# tx_board.net
KiCad netlist of a schematic drawn in EAGLE
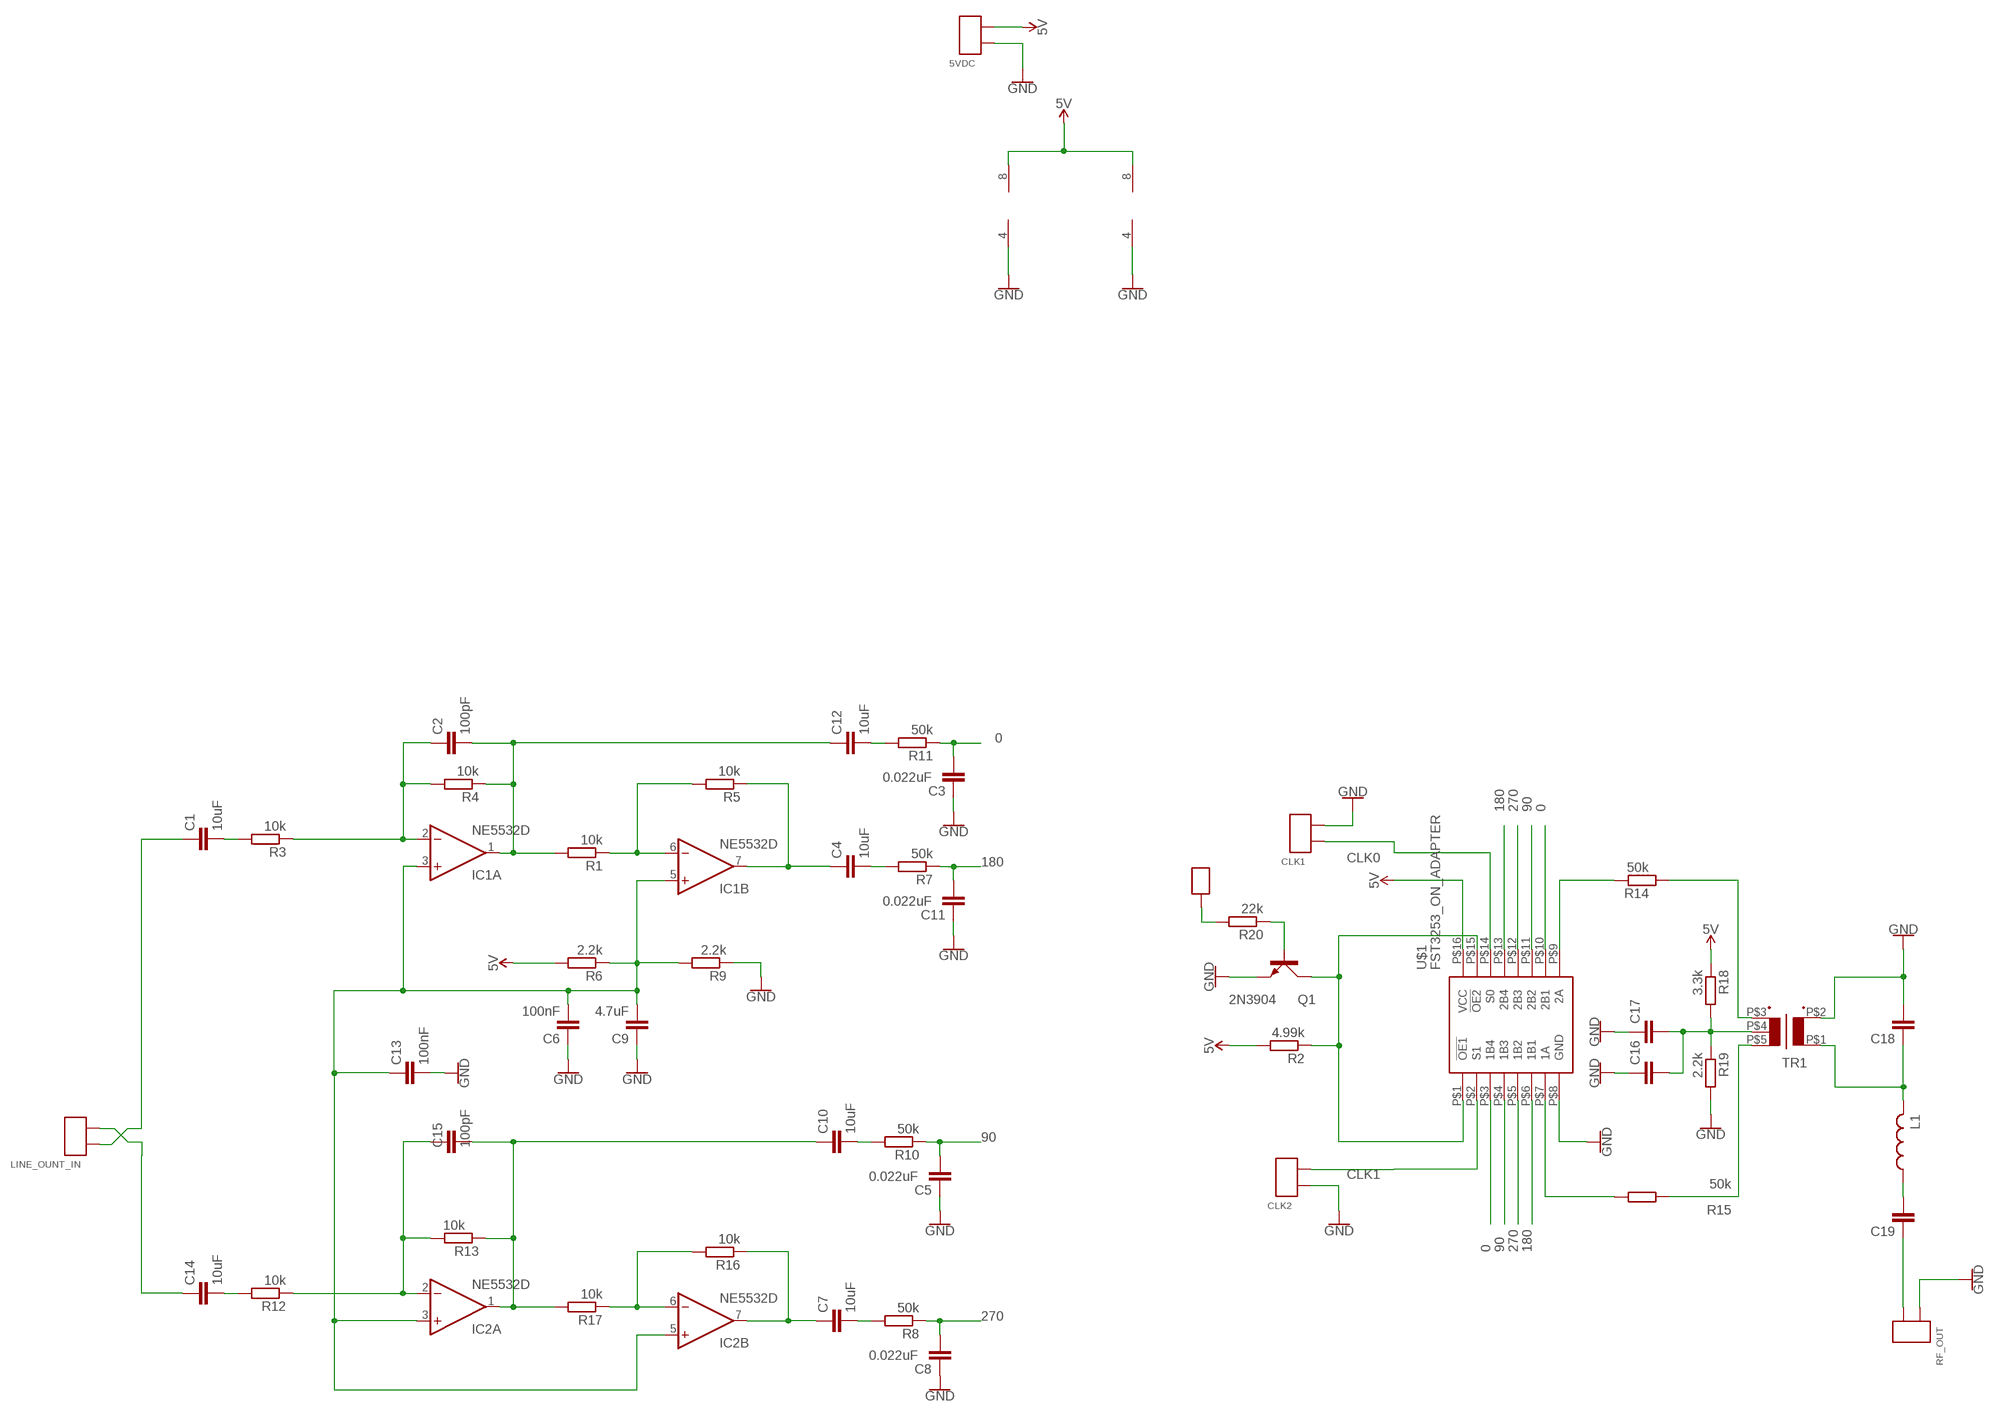
[diagram p0: schematic, sheet 1]

(export (version "E")
  (design (tool "Eeschema 10.0.6"))
  (components
    (comp (ref "5VDC")
      (value "2X_SMD_PTH_PIN")
      (footprint "eagle-import:2X_SMD_PTH")
      (libsource (lib "eagle-import") (part "2X_SMD_PTH_PIN"))
    )
    (comp (ref "C1")
      (value "10uF")
      (footprint "eagle-import:C0805")
      (libsource (lib "eagle-import") (part "C_0805_SMD"))
    )
    (comp (ref "C2")
      (value "100pF")
      (footprint "eagle-import:C0805")
      (libsource (lib "eagle-import") (part "C_0805_SMD"))
    )
    (comp (ref "C3")
      (value "0.022uF")
      (footprint "eagle-import:C0805")
      (libsource (lib "eagle-import") (part "C_0805_SMD"))
    )
    (comp (ref "C4")
      (value "10uF")
      (footprint "eagle-import:C0805")
      (libsource (lib "eagle-import") (part "C_0805_SMD"))
    )
    (comp (ref "C5")
      (value "0.022uF")
      (footprint "eagle-import:C0805")
      (libsource (lib "eagle-import") (part "C_0805_SMD"))
    )
    (comp (ref "C6")
      (value "100nF")
      (footprint "eagle-import:C0805")
      (libsource (lib "eagle-import") (part "C_0805_SMD"))
    )
    (comp (ref "C7")
      (value "10uF")
      (footprint "eagle-import:C0805")
      (libsource (lib "eagle-import") (part "C_0805_SMD"))
    )
    (comp (ref "C8")
      (value "0.022uF")
      (footprint "eagle-import:C0805")
      (libsource (lib "eagle-import") (part "C_0805_SMD"))
    )
    (comp (ref "C9")
      (value "4.7uF")
      (footprint "eagle-import:C0805")
      (libsource (lib "eagle-import") (part "C_0805_SMD"))
    )
    (comp (ref "C10")
      (value "10uF")
      (footprint "eagle-import:C0805")
      (libsource (lib "eagle-import") (part "C_0805_SMD"))
    )
    (comp (ref "C11")
      (value "0.022uF")
      (footprint "eagle-import:C0805")
      (libsource (lib "eagle-import") (part "C_0805_SMD"))
    )
    (comp (ref "C12")
      (value "10uF")
      (footprint "eagle-import:C0805")
      (libsource (lib "eagle-import") (part "C_0805_SMD"))
    )
    (comp (ref "C13")
      (value "100nF")
      (footprint "eagle-import:C0805")
      (libsource (lib "eagle-import") (part "C_0805_SMD"))
    )
    (comp (ref "C14")
      (value "10uF")
      (footprint "eagle-import:C0805")
      (libsource (lib "eagle-import") (part "C_0805_SMD"))
    )
    (comp (ref "C15")
      (value "100pF")
      (footprint "eagle-import:C0805")
      (libsource (lib "eagle-import") (part "C_0805_SMD"))
    )
    (comp (ref "C16")
      (value "C_0805_SMD")
      (footprint "eagle-import:C0805")
      (libsource (lib "eagle-import") (part "C_0805_SMD"))
    )
    (comp (ref "C17")
      (value "C_0805_SMD")
      (footprint "eagle-import:C0805")
      (libsource (lib "eagle-import") (part "C_0805_SMD"))
    )
    (comp (ref "C18")
      (value "C_0805_PTH")
      (footprint "eagle-import:C0805K")
      (libsource (lib "eagle-import") (part "C_0805_PTH"))
    )
    (comp (ref "C19")
      (value "C_0805_PTH")
      (footprint "eagle-import:C0805K")
      (libsource (lib "eagle-import") (part "C_0805_PTH"))
    )
    (comp (ref "CLK1")
      (value "2X_SMD_PTH_PIN")
      (footprint "eagle-import:2X_SMD_PTH")
      (libsource (lib "eagle-import") (part "2X_SMD_PTH_PIN"))
    )
    (comp (ref "CLK2")
      (value "2X_SMD_PTH_PIN")
      (footprint "eagle-import:2X_SMD_PTH")
      (libsource (lib "eagle-import") (part "2X_SMD_PTH_PIN"))
    )
    (comp (ref "IC1")
      (value "NE5532D")
      (footprint "eagle-import:SO08")
      (libsource (lib "eagle-import") (part "NE5532D"))
    )
    (comp (ref "IC2")
      (value "NE5532D")
      (footprint "eagle-import:SO08")
      (libsource (lib "eagle-import") (part "NE5532D"))
    )
    (comp (ref "L1")
      (value "L_0805_PTH")
      (footprint "eagle-import:M0805")
      (libsource (lib "eagle-import") (part "L_0805_PTH"))
    )
    (comp (ref "LINE_OUNT_IN")
      (value "2X_SMD_PTH_PIN")
      (footprint "eagle-import:2X_SMD_PTH")
      (libsource (lib "eagle-import") (part "2X_SMD_PTH_PIN"))
    )
    (comp (ref "Q1")
      (value "2N3904")
      (footprint "eagle-import:TO92D")
      (libsource (lib "eagle-import") (part "2N3904"))
    )
    (comp (ref "R1")
      (value "10k")
      (footprint "eagle-import:R0805W")
      (libsource (lib "eagle-import") (part "R_0805_SMD"))
    )
    (comp (ref "R2")
      (value "4.99k")
      (footprint "eagle-import:R0805W")
      (libsource (lib "eagle-import") (part "R_0805_SMD"))
    )
    (comp (ref "R3")
      (value "10k")
      (footprint "eagle-import:R0805W")
      (libsource (lib "eagle-import") (part "R_0805_SMD"))
    )
    (comp (ref "R4")
      (value "10k")
      (footprint "eagle-import:R0805W")
      (libsource (lib "eagle-import") (part "R_0805_SMD"))
    )
    (comp (ref "R5")
      (value "10k")
      (footprint "eagle-import:R0805W")
      (libsource (lib "eagle-import") (part "R_0805_SMD"))
    )
    (comp (ref "R6")
      (value "2.2k")
      (footprint "eagle-import:0204_7")
      (libsource (lib "eagle-import") (part "R-EU_0204/7"))
    )
    (comp (ref "R7")
      (value "50k")
      (footprint "eagle-import:R0805W")
      (libsource (lib "eagle-import") (part "R_0805_SMD"))
    )
    (comp (ref "R8")
      (value "50k")
      (footprint "eagle-import:R0805W")
      (libsource (lib "eagle-import") (part "R_0805_SMD"))
    )
    (comp (ref "R9")
      (value "2.2k")
      (footprint "eagle-import:R0805W")
      (libsource (lib "eagle-import") (part "R_0805_SMD"))
    )
    (comp (ref "R10")
      (value "50k")
      (footprint "eagle-import:R0805W")
      (libsource (lib "eagle-import") (part "R_0805_SMD"))
    )
    (comp (ref "R11")
      (value "50k")
      (footprint "eagle-import:R0805W")
      (libsource (lib "eagle-import") (part "R_0805_SMD"))
    )
    (comp (ref "R12")
      (value "10k")
      (footprint "eagle-import:R0805W")
      (libsource (lib "eagle-import") (part "R_0805_SMD"))
    )
    (comp (ref "R13")
      (value "10k")
      (footprint "eagle-import:R0805W")
      (libsource (lib "eagle-import") (part "R_0805_SMD"))
    )
    (comp (ref "R14")
      (value "50k")
      (footprint "eagle-import:R0805W")
      (libsource (lib "eagle-import") (part "R_0805_SMD"))
    )
    (comp (ref "R15")
      (value "50k")
      (footprint "eagle-import:R0805W")
      (libsource (lib "eagle-import") (part "R_0805_SMD"))
    )
    (comp (ref "R16")
      (value "10k")
      (footprint "eagle-import:R0805W")
      (libsource (lib "eagle-import") (part "R_0805_SMD"))
    )
    (comp (ref "R17")
      (value "10k")
      (footprint "eagle-import:R0805W")
      (libsource (lib "eagle-import") (part "R_0805_SMD"))
    )
    (comp (ref "R18")
      (value "3.3k")
      (footprint "eagle-import:R0805W")
      (libsource (lib "eagle-import") (part "R_0805_SMD"))
    )
    (comp (ref "R19")
      (value "2.2k")
      (footprint "eagle-import:R0805W")
      (libsource (lib "eagle-import") (part "R_0805_SMD"))
    )
    (comp (ref "R20")
      (value "22k")
      (footprint "eagle-import:R0805W")
      (libsource (lib "eagle-import") (part "R_0805_SMD"))
    )
    (comp (ref "RF_OUT")
      (value "2X_SMD_PTH_PIN")
      (footprint "eagle-import:2X_SMD_PTH")
      (libsource (lib "eagle-import") (part "2X_SMD_PTH_PIN"))
    )
    (comp (ref "TR1")
      (value "5PIN_TRANSFORMER")
      (footprint "eagle-import:5PIN_TRANSFORMER")
      (libsource (lib "eagle-import") (part "5PIN_TRANSFORMER"))
    )
    (comp (ref "TX_DISABLE")
      (value "SMD_PTH_PIN")
      (footprint "eagle-import:SMD_PTH_PIN")
      (libsource (lib "eagle-import") (part "SMD_PTH_PIN"))
    )
    (comp (ref "U$1")
      (value "FST3253_ON_ADAPTER")
      (footprint "eagle-import:SSOP16_ADAPTER")
      (libsource (lib "eagle-import") (part "FST3253_ON_ADAPTER"))
    )
  )
  (nets
    (net (code "1") (name "/0") (class "Default")
      (node (ref "C3") (pin "2") (pinfunction "2_2") (pintype "passive"))
      (node (ref "R11") (pin "1") (pinfunction "1_1") (pintype "passive"))
      (node (ref "U$1") (pin "P$10") (pinfunction "2B1_P$10") (pintype "bidirectional"))
      (node (ref "U$1") (pin "P$3") (pinfunction "1B4_P$3") (pintype "bidirectional"))
    )
    (net (code "2") (name "/90") (class "Default")
      (node (ref "C5") (pin "2") (pinfunction "2_2") (pintype "passive"))
      (node (ref "R10") (pin "1") (pinfunction "1_1") (pintype "passive"))
      (node (ref "U$1") (pin "P$11") (pinfunction "2B2_P$11") (pintype "bidirectional"))
      (node (ref "U$1") (pin "P$4") (pinfunction "1B3_P$4") (pintype "bidirectional"))
    )
    (net (code "3") (name "/180") (class "Default")
      (node (ref "C11") (pin "2") (pinfunction "2_2") (pintype "passive"))
      (node (ref "R7") (pin "1") (pinfunction "1_1") (pintype "passive"))
      (node (ref "U$1") (pin "P$13") (pinfunction "2B4_P$13") (pintype "bidirectional"))
      (node (ref "U$1") (pin "P$6") (pinfunction "1B1_P$6") (pintype "bidirectional"))
    )
    (net (code "4") (name "/270") (class "Default")
      (node (ref "C8") (pin "2") (pinfunction "2_2") (pintype "passive"))
      (node (ref "R8") (pin "1") (pinfunction "1_1") (pintype "passive"))
      (node (ref "U$1") (pin "P$12") (pinfunction "2B3_P$12") (pintype "bidirectional"))
      (node (ref "U$1") (pin "P$5") (pinfunction "1B2_P$5") (pintype "bidirectional"))
    )
    (net (code "5") (name "/CLK0") (class "Default")
      (node (ref "CLK1") (pin "P$1") (pinfunction "PIN0_P$1") (pintype "bidirectional"))
      (node (ref "CLK1") (pin "T$1") (pinfunction "PIN0_T$1") (pintype "bidirectional"))
      (node (ref "U$1") (pin "P$14") (pinfunction "S0_P$14") (pintype "bidirectional"))
    )
    (net (code "6") (name "/CLK1") (class "Default")
      (node (ref "CLK2") (pin "P$2") (pinfunction "PIN1_P$2") (pintype "bidirectional"))
      (node (ref "CLK2") (pin "T$2") (pinfunction "PIN1_T$2") (pintype "bidirectional"))
      (node (ref "U$1") (pin "P$2") (pinfunction "S1_P$2") (pintype "bidirectional"))
    )
    (net (code "7") (name "5V") (class "Default")
      (node (ref "5VDC") (pin "P$2") (pinfunction "PIN1_P$2") (pintype "bidirectional"))
      (node (ref "5VDC") (pin "T$2") (pinfunction "PIN1_T$2") (pintype "bidirectional"))
      (node (ref "IC1") (pin "8") (pinfunction "V+_8") (pintype "power_in"))
      (node (ref "IC2") (pin "8") (pinfunction "V+_8") (pintype "power_in"))
      (node (ref "R18") (pin "1") (pinfunction "1_1") (pintype "passive"))
      (node (ref "R2") (pin "2") (pinfunction "2_2") (pintype "passive"))
      (node (ref "R6") (pin "2") (pinfunction "2_2") (pintype "passive"))
      (node (ref "U$1") (pin "P$16") (pinfunction "VCC_P$16") (pintype "power_in"))
    )
    (net (code "8") (name "GND") (class "Default")
      (node (ref "5VDC") (pin "P$1") (pinfunction "PIN0_P$1") (pintype "bidirectional"))
      (node (ref "5VDC") (pin "T$1") (pinfunction "PIN0_T$1") (pintype "bidirectional"))
      (node (ref "C11") (pin "1") (pinfunction "1_1") (pintype "passive"))
      (node (ref "C13") (pin "2") (pinfunction "2_2") (pintype "passive"))
      (node (ref "C16") (pin "1") (pinfunction "1_1") (pintype "passive"))
      (node (ref "C17") (pin "1") (pinfunction "1_1") (pintype "passive"))
      (node (ref "C18") (pin "2") (pinfunction "2_2") (pintype "passive"))
      (node (ref "C18") (pin "P$2") (pinfunction "2_P$2") (pintype "passive"))
      (node (ref "C3") (pin "1") (pinfunction "1_1") (pintype "passive"))
      (node (ref "C5") (pin "1") (pinfunction "1_1") (pintype "passive"))
      (node (ref "C6") (pin "1") (pinfunction "1_1") (pintype "passive"))
      (node (ref "C8") (pin "1") (pinfunction "1_1") (pintype "passive"))
      (node (ref "C9") (pin "1") (pinfunction "1_1") (pintype "passive"))
      (node (ref "CLK1") (pin "P$2") (pinfunction "PIN1_P$2") (pintype "bidirectional"))
      (node (ref "CLK1") (pin "T$2") (pinfunction "PIN1_T$2") (pintype "bidirectional"))
      (node (ref "CLK2") (pin "P$1") (pinfunction "PIN0_P$1") (pintype "bidirectional"))
      (node (ref "CLK2") (pin "T$1") (pinfunction "PIN0_T$1") (pintype "bidirectional"))
      (node (ref "IC1") (pin "4") (pinfunction "V-_4") (pintype "power_in"))
      (node (ref "IC2") (pin "4") (pinfunction "V-_4") (pintype "power_in"))
      (node (ref "Q1") (pin "E") (pinfunction "E_E") (pintype "passive"))
      (node (ref "R19") (pin "2") (pinfunction "2_2") (pintype "passive"))
      (node (ref "R9") (pin "1") (pinfunction "1_1") (pintype "passive"))
      (node (ref "RF_OUT") (pin "P$1") (pinfunction "PIN0_P$1") (pintype "bidirectional"))
      (node (ref "RF_OUT") (pin "T$1") (pinfunction "PIN0_T$1") (pintype "bidirectional"))
      (node (ref "TR1") (pin "P$2") (pinfunction "2_P$2") (pintype "passive"))
      (node (ref "U$1") (pin "P$8") (pinfunction "GND_P$8") (pintype "power_in"))
    )
    (net (code "9") (name "Net-(C1-Pad1)") (class "Default")
      (node (ref "C1") (pin "1") (pinfunction "1_1") (pintype "passive"))
      (node (ref "LINE_OUNT_IN") (pin "P$1") (pinfunction "PIN0_P$1") (pintype "bidirectional"))
      (node (ref "LINE_OUNT_IN") (pin "T$1") (pinfunction "PIN0_T$1") (pintype "bidirectional"))
    )
    (net (code "10") (name "Net-(C1-Pad2)") (class "Default")
      (node (ref "C1") (pin "2") (pinfunction "2_2") (pintype "passive"))
      (node (ref "R3") (pin "2") (pinfunction "2_2") (pintype "passive"))
    )
    (net (code "11") (name "Net-(C4-Pad2)") (class "Default")
      (node (ref "C4") (pin "2") (pinfunction "2_2") (pintype "passive"))
      (node (ref "R7") (pin "2") (pinfunction "2_2") (pintype "passive"))
    )
    (net (code "12") (name "Net-(C7-Pad2)") (class "Default")
      (node (ref "C7") (pin "2") (pinfunction "2_2") (pintype "passive"))
      (node (ref "R8") (pin "2") (pinfunction "2_2") (pintype "passive"))
    )
    (net (code "13") (name "Net-(C10-Pad2)") (class "Default")
      (node (ref "C10") (pin "2") (pinfunction "2_2") (pintype "passive"))
      (node (ref "R10") (pin "2") (pinfunction "2_2") (pintype "passive"))
    )
    (net (code "14") (name "Net-(C12-Pad2)") (class "Default")
      (node (ref "C12") (pin "2") (pinfunction "2_2") (pintype "passive"))
      (node (ref "R11") (pin "2") (pinfunction "2_2") (pintype "passive"))
    )
    (net (code "15") (name "Net-(C14-Pad1)") (class "Default")
      (node (ref "C14") (pin "1") (pinfunction "1_1") (pintype "passive"))
      (node (ref "LINE_OUNT_IN") (pin "P$2") (pinfunction "PIN1_P$2") (pintype "bidirectional"))
      (node (ref "LINE_OUNT_IN") (pin "T$2") (pinfunction "PIN1_T$2") (pintype "bidirectional"))
    )
    (net (code "16") (name "Net-(C14-Pad2)") (class "Default")
      (node (ref "C14") (pin "2") (pinfunction "2_2") (pintype "passive"))
      (node (ref "R12") (pin "2") (pinfunction "2_2") (pintype "passive"))
    )
    (net (code "17") (name "Net-(C19-1-PadP$1)") (class "Default")
      (node (ref "C19") (pin "1") (pinfunction "1_1") (pintype "passive"))
      (node (ref "C19") (pin "P$1") (pinfunction "1_P$1") (pintype "passive"))
      (node (ref "RF_OUT") (pin "P$2") (pinfunction "PIN1_P$2") (pintype "bidirectional"))
      (node (ref "RF_OUT") (pin "T$2") (pinfunction "PIN1_T$2") (pintype "bidirectional"))
    )
    (net (code "18") (name "Net-(C19-2-PadP$2)") (class "Default")
      (node (ref "C19") (pin "2") (pinfunction "2_2") (pintype "passive"))
      (node (ref "C19") (pin "P$2") (pinfunction "2_P$2") (pintype "passive"))
      (node (ref "L1") (pin "1") (pinfunction "1_1") (pintype "passive"))
      (node (ref "L1") (pin "P$1") (pinfunction "1_P$1") (pintype "passive"))
    )
    (net (code "19") (name "Net-(IC1A-+IN)") (class "Default")
      (node (ref "C13") (pin "1") (pinfunction "1_1") (pintype "passive"))
      (node (ref "C6") (pin "2") (pinfunction "2_2") (pintype "passive"))
      (node (ref "C9") (pin "2") (pinfunction "2_2") (pintype "passive"))
      (node (ref "IC1") (pin "3") (pinfunction "+IN_3") (pintype "input"))
      (node (ref "IC1") (pin "5") (pinfunction "+IN_5") (pintype "input"))
      (node (ref "IC2") (pin "3") (pinfunction "+IN_3") (pintype "input"))
      (node (ref "IC2") (pin "5") (pinfunction "+IN_5") (pintype "input"))
      (node (ref "R6") (pin "1") (pinfunction "1_1") (pintype "passive"))
      (node (ref "R9") (pin "2") (pinfunction "2_2") (pintype "passive"))
    )
    (net (code "20") (name "Net-(IC1A--IN)") (class "Default")
      (node (ref "C2") (pin "1") (pinfunction "1_1") (pintype "passive"))
      (node (ref "IC1") (pin "2") (pinfunction "-IN_2") (pintype "input"))
      (node (ref "R3") (pin "1") (pinfunction "1_1") (pintype "passive"))
      (node (ref "R4") (pin "2") (pinfunction "2_2") (pintype "passive"))
    )
    (net (code "21") (name "Net-(IC1A-OUT)") (class "Default")
      (node (ref "C12") (pin "1") (pinfunction "1_1") (pintype "passive"))
      (node (ref "C2") (pin "2") (pinfunction "2_2") (pintype "passive"))
      (node (ref "IC1") (pin "1") (pinfunction "OUT_1") (pintype "output"))
      (node (ref "R1") (pin "2") (pinfunction "2_2") (pintype "passive"))
      (node (ref "R4") (pin "1") (pinfunction "1_1") (pintype "passive"))
    )
    (net (code "22") (name "Net-(IC1B--IN)") (class "Default")
      (node (ref "IC1") (pin "6") (pinfunction "-IN_6") (pintype "input"))
      (node (ref "R1") (pin "1") (pinfunction "1_1") (pintype "passive"))
      (node (ref "R5") (pin "2") (pinfunction "2_2") (pintype "passive"))
    )
    (net (code "23") (name "Net-(IC1B-OUT)") (class "Default")
      (node (ref "C4") (pin "1") (pinfunction "1_1") (pintype "passive"))
      (node (ref "IC1") (pin "7") (pinfunction "OUT_7") (pintype "output"))
      (node (ref "R5") (pin "1") (pinfunction "1_1") (pintype "passive"))
    )
    (net (code "24") (name "Net-(IC2A--IN)") (class "Default")
      (node (ref "C15") (pin "1") (pinfunction "1_1") (pintype "passive"))
      (node (ref "IC2") (pin "2") (pinfunction "-IN_2") (pintype "input"))
      (node (ref "R12") (pin "1") (pinfunction "1_1") (pintype "passive"))
      (node (ref "R13") (pin "2") (pinfunction "2_2") (pintype "passive"))
    )
    (net (code "25") (name "Net-(IC2A-OUT)") (class "Default")
      (node (ref "C10") (pin "1") (pinfunction "1_1") (pintype "passive"))
      (node (ref "C15") (pin "2") (pinfunction "2_2") (pintype "passive"))
      (node (ref "IC2") (pin "1") (pinfunction "OUT_1") (pintype "output"))
      (node (ref "R13") (pin "1") (pinfunction "1_1") (pintype "passive"))
      (node (ref "R17") (pin "2") (pinfunction "2_2") (pintype "passive"))
    )
    (net (code "26") (name "Net-(IC2B--IN)") (class "Default")
      (node (ref "IC2") (pin "6") (pinfunction "-IN_6") (pintype "input"))
      (node (ref "R16") (pin "2") (pinfunction "2_2") (pintype "passive"))
      (node (ref "R17") (pin "1") (pinfunction "1_1") (pintype "passive"))
    )
    (net (code "27") (name "Net-(IC2B-OUT)") (class "Default")
      (node (ref "C7") (pin "1") (pinfunction "1_1") (pintype "passive"))
      (node (ref "IC2") (pin "7") (pinfunction "OUT_7") (pintype "output"))
      (node (ref "R16") (pin "1") (pinfunction "1_1") (pintype "passive"))
    )
    (net (code "28") (name "Net-(Q1-PadB)") (class "Default")
      (node (ref "Q1") (pin "B") (pinfunction "B_B") (pintype "passive"))
      (node (ref "R20") (pin "1") (pinfunction "1_1") (pintype "passive"))
    )
    (net (code "29") (name "Net-(R20-Pad2)") (class "Default")
      (node (ref "R20") (pin "2") (pinfunction "2_2") (pintype "passive"))
      (node (ref "TX_DISABLE") (pin "P$1") (pinfunction "P$1_P$1") (pintype "bidirectional"))
      (node (ref "TX_DISABLE") (pin "P$2") (pinfunction "P$1_P$2") (pintype "bidirectional"))
    )
    (net (code "30") (name "Net-(TR1-1)") (class "Default")
      (node (ref "C18") (pin "1") (pinfunction "1_1") (pintype "passive"))
      (node (ref "C18") (pin "P$1") (pinfunction "1_P$1") (pintype "passive"))
      (node (ref "L1") (pin "2") (pinfunction "2_2") (pintype "passive"))
      (node (ref "L1") (pin "P$2") (pinfunction "2_P$2") (pintype "passive"))
      (node (ref "TR1") (pin "P$1") (pinfunction "1_P$1") (pintype "passive"))
    )
    (net (code "31") (name "Net-(TR1-3)") (class "Default")
      (node (ref "R14") (pin "1") (pinfunction "1_1") (pintype "passive"))
      (node (ref "TR1") (pin "P$3") (pinfunction "3_P$3") (pintype "passive"))
    )
    (net (code "32") (name "Net-(TR1-4)") (class "Default")
      (node (ref "C16") (pin "2") (pinfunction "2_2") (pintype "passive"))
      (node (ref "C17") (pin "2") (pinfunction "2_2") (pintype "passive"))
      (node (ref "R18") (pin "2") (pinfunction "2_2") (pintype "passive"))
      (node (ref "R19") (pin "1") (pinfunction "1_1") (pintype "passive"))
      (node (ref "TR1") (pin "P$4") (pinfunction "4_P$4") (pintype "passive"))
    )
    (net (code "33") (name "Net-(TR1-5)") (class "Default")
      (node (ref "R15") (pin "1") (pinfunction "1_1") (pintype "passive"))
      (node (ref "TR1") (pin "P$5") (pinfunction "5_P$5") (pintype "passive"))
    )
    (net (code "34") (name "Net-(U$1-1A)") (class "Default")
      (node (ref "R15") (pin "2") (pinfunction "2_2") (pintype "passive"))
      (node (ref "U$1") (pin "P$7") (pinfunction "1A_P$7") (pintype "bidirectional"))
    )
    (net (code "35") (name "Net-(U$1-2A)") (class "Default")
      (node (ref "R14") (pin "2") (pinfunction "2_2") (pintype "passive"))
      (node (ref "U$1") (pin "P$9") (pinfunction "2A_P$9") (pintype "bidirectional"))
    )
    (net (code "36") (name "Net-(U$1-~{OE1})") (class "Default")
      (node (ref "Q1") (pin "C") (pinfunction "C_C") (pintype "passive"))
      (node (ref "R2") (pin "1") (pinfunction "1_1") (pintype "passive"))
      (node (ref "U$1") (pin "P$1") (pinfunction "~{OE1}_P$1") (pintype "bidirectional"))
      (node (ref "U$1") (pin "P$15") (pinfunction "~{OE2}_P$15") (pintype "bidirectional"))
    )
  )
)
